# attinyboard.net
KiCad netlist of a schematic drawn in EAGLE
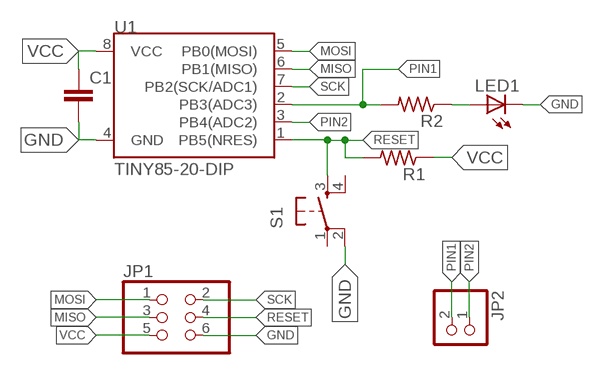
[diagram p0: schematic, sheet 1]

(export (version "E")
  (design (tool "Eeschema 10.0.6"))
  (components
    (comp (ref "C1")
      (value "C-EU025-030X050")
      (footprint "eagle-import:C025-030X050")
      (libsource (lib "eagle-import") (part "C-EU025-030X050"))
    )
    (comp (ref "JP1")
      (value "PINHD-2X3")
      (footprint "eagle-import:2X03")
      (libsource (lib "eagle-import") (part "PINHD-2X3"))
    )
    (comp (ref "JP2")
      (value "PINHD-1X2")
      (footprint "eagle-import:1X02")
      (libsource (lib "eagle-import") (part "PINHD-1X2"))
    )
    (comp (ref "LED1")
      (value "LED5MM")
      (footprint "eagle-import:LED5MM")
      (libsource (lib "eagle-import") (part "LED5MM"))
    )
    (comp (ref "R1")
      (value "R-US_0204/7")
      (footprint "eagle-import:0204_7")
      (libsource (lib "eagle-import") (part "R-US_0204/7"))
    )
    (comp (ref "R2")
      (value "R-US_0204/7")
      (footprint "eagle-import:0204_7")
      (libsource (lib "eagle-import") (part "R-US_0204/7"))
    )
    (comp (ref "S1")
      (value "TAC_SWITCHPTH")
      (footprint "eagle-import:TACTILE-PTH")
      (libsource (lib "eagle-import") (part "TAC_SWITCHPTH"))
    )
    (comp (ref "U1")
      (value "TINY85-20-DIP")
      (footprint "eagle-import:DIP08")
      (libsource (lib "eagle-import") (part "ATTINY45TINY85-20-DIP"))
    )
  )
  (nets
    (net (code "1") (name "GND") (class "Default")
      (node (ref "C1") (pin "2") (pinfunction "2_2") (pintype "passive"))
      (node (ref "JP1") (pin "6") (pinfunction "6_6") (pintype "passive"))
      (node (ref "LED1") (pin "K") (pinfunction "C_K") (pintype "passive"))
      (node (ref "S1") (pin "2") (pinfunction "2_2") (pintype "passive"))
      (node (ref "U1") (pin "4") (pinfunction "GND_4") (pintype "bidirectional"))
    )
    (net (code "2") (name "MISO") (class "Default")
      (node (ref "JP1") (pin "3") (pinfunction "3_3") (pintype "passive"))
      (node (ref "U1") (pin "6") (pinfunction "PB1(MISO)_6") (pintype "bidirectional"))
    )
    (net (code "3") (name "MOSI") (class "Default")
      (node (ref "JP1") (pin "1") (pinfunction "1_1") (pintype "passive"))
      (node (ref "U1") (pin "5") (pinfunction "PB0(MOSI)_5") (pintype "bidirectional"))
    )
    (net (code "4") (name "Net-(LED1-PadA)") (class "Default")
      (node (ref "LED1") (pin "A") (pinfunction "A_A") (pintype "passive"))
      (node (ref "R2") (pin "1") (pinfunction "1_1") (pintype "passive"))
    )
    (net (code "5") (name "PIN1") (class "Default")
      (node (ref "JP2") (pin "2") (pinfunction "2_2") (pintype "passive"))
      (node (ref "R2") (pin "2") (pinfunction "2_2") (pintype "passive"))
      (node (ref "U1") (pin "2") (pinfunction "PB3(ADC3)_2") (pintype "bidirectional"))
    )
    (net (code "6") (name "PIN2") (class "Default")
      (node (ref "JP2") (pin "1") (pinfunction "1_1") (pintype "passive"))
      (node (ref "U1") (pin "3") (pinfunction "PB4(ADC2)_3") (pintype "bidirectional"))
    )
    (net (code "7") (name "RESET") (class "Default")
      (node (ref "JP1") (pin "4") (pinfunction "4_4") (pintype "passive"))
      (node (ref "R1") (pin "2") (pinfunction "2_2") (pintype "passive"))
      (node (ref "S1") (pin "3") (pinfunction "3_3") (pintype "passive"))
      (node (ref "U1") (pin "1") (pinfunction "PB5(NRES)_1") (pintype "bidirectional"))
    )
    (net (code "8") (name "SCK") (class "Default")
      (node (ref "JP1") (pin "2") (pinfunction "2_2") (pintype "passive"))
      (node (ref "U1") (pin "7") (pinfunction "PB2(SCK/ADC1)_7") (pintype "bidirectional"))
    )
    (net (code "9") (name "VCC") (class "Default")
      (node (ref "C1") (pin "1") (pinfunction "1_1") (pintype "passive"))
      (node (ref "JP1") (pin "5") (pinfunction "5_5") (pintype "passive"))
      (node (ref "R1") (pin "1") (pinfunction "1_1") (pintype "passive"))
      (node (ref "U1") (pin "8") (pinfunction "VCC_8") (pintype "bidirectional"))
    )
    (net (code "10") (name "unconnected-(S1-Pad1)") (class "Default")
      (node (ref "S1") (pin "1") (pinfunction "1_1") (pintype "passive"))
    )
    (net (code "11") (name "unconnected-(S1-Pad4)") (class "Default")
      (node (ref "S1") (pin "4") (pinfunction "4_4") (pintype "passive"))
    )
  )
)
